# Airsensor.net
KiCad netlist of a schematic drawn in EAGLE
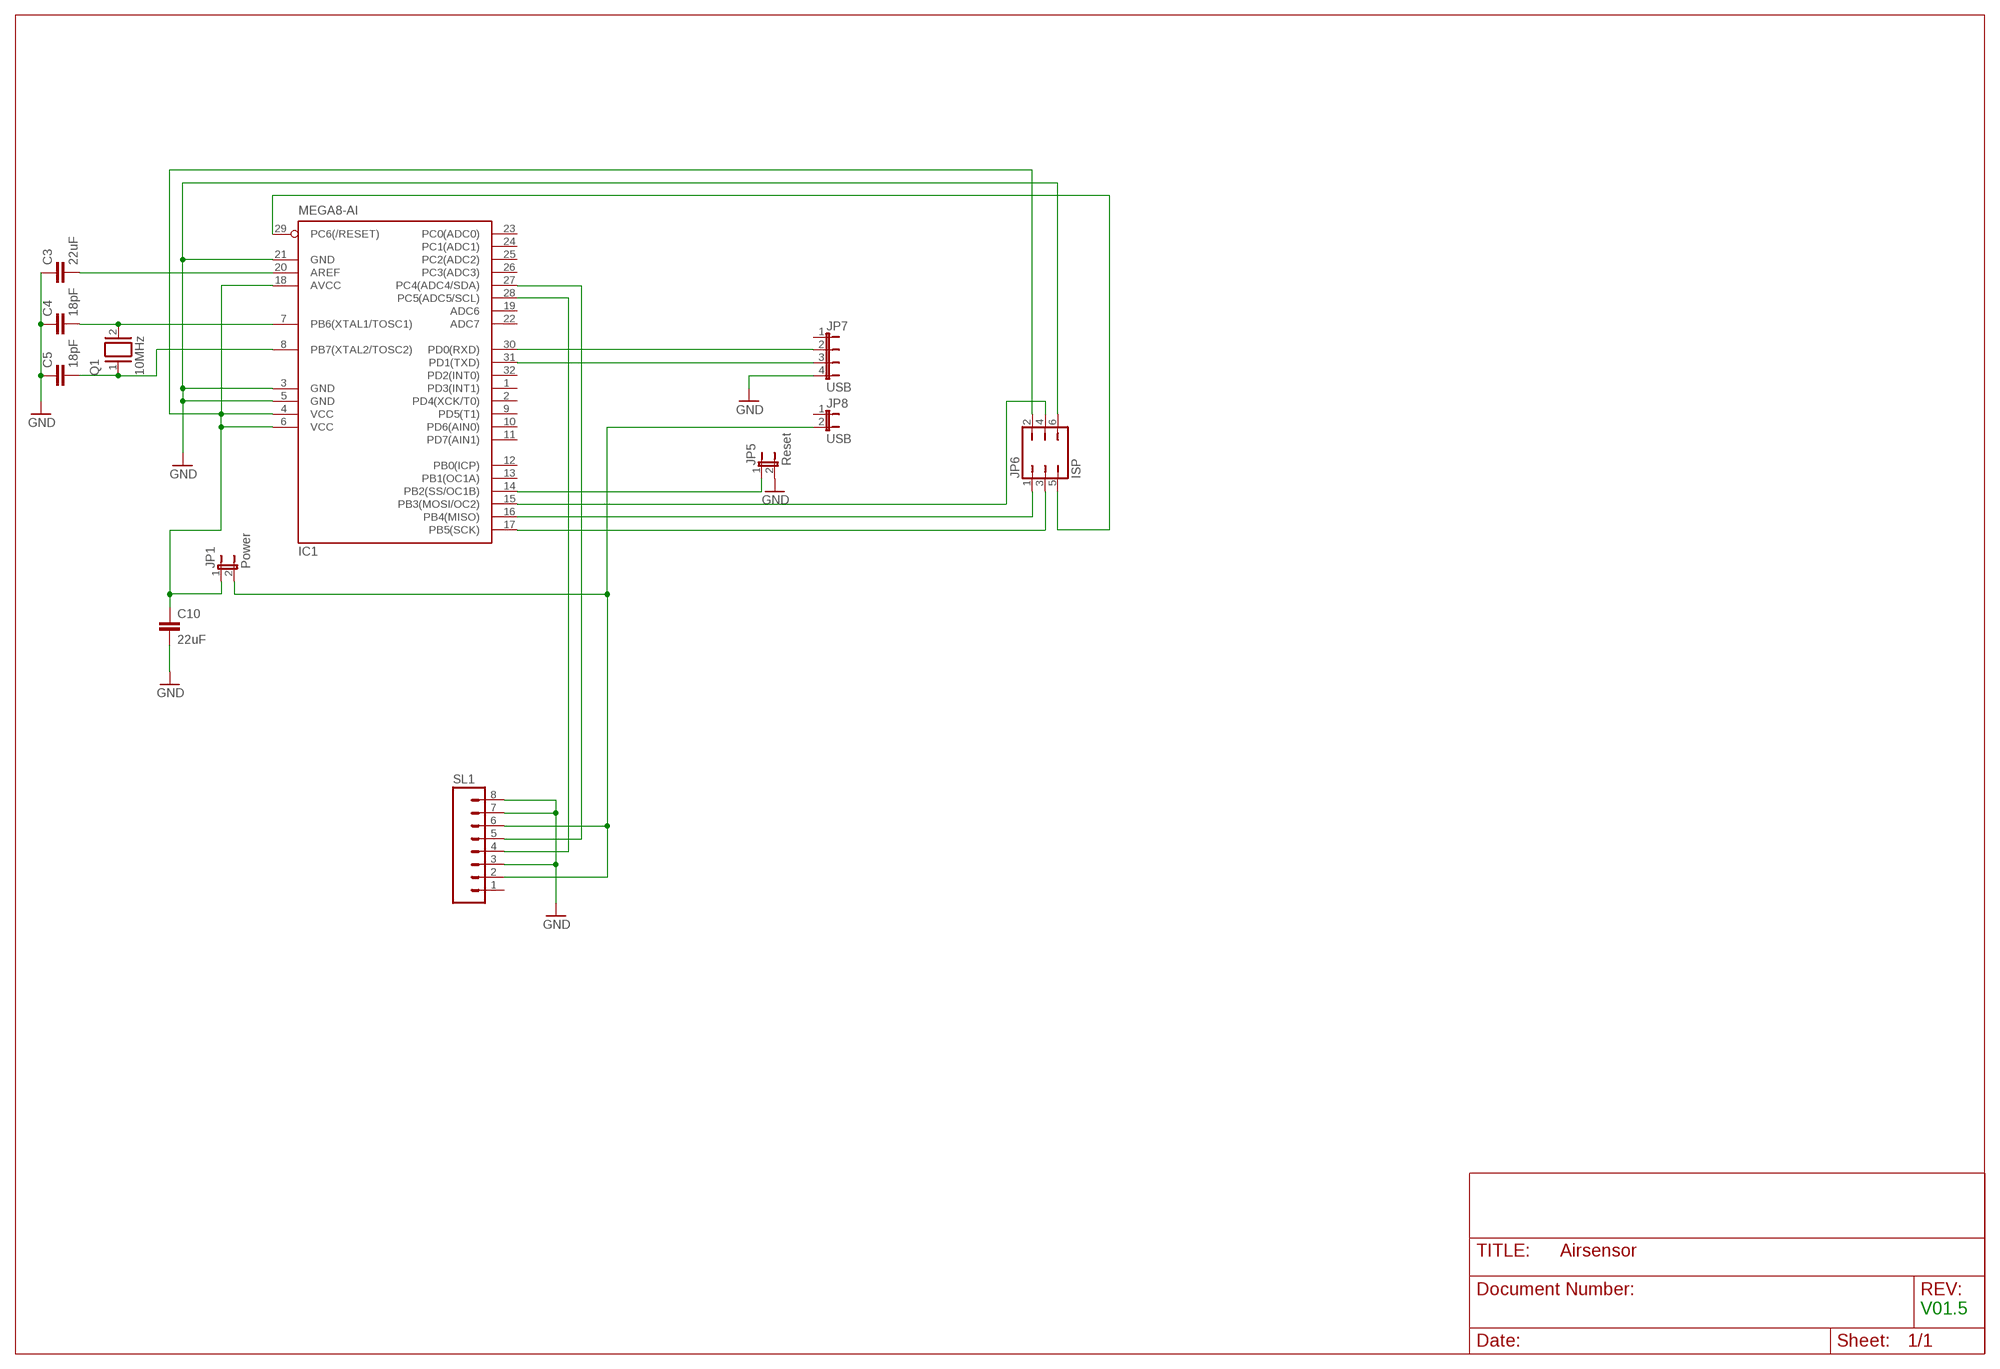
[diagram p0: schematic, sheet 1]

(export (version "E")
  (design (tool "Eeschema 10.0.6"))
  (components
    (comp (ref "C3")
      (value "22uF")
      (footprint "eagle-import:C1206")
      (libsource (lib "eagle-import") (part "C-EUC1206"))
    )
    (comp (ref "C4")
      (value "18pF")
      (footprint "eagle-import:C025-025X050")
      (libsource (lib "eagle-import") (part "resistor_C-EU025-025X050"))
    )
    (comp (ref "C5")
      (value "18pF")
      (footprint "eagle-import:C025-025X050")
      (libsource (lib "eagle-import") (part "resistor_C-EU025-025X050"))
    )
    (comp (ref "C10")
      (value "22uF")
      (footprint "eagle-import:C1206")
      (libsource (lib "eagle-import") (part "C-EUC1206"))
    )
    (comp (ref "IC1")
      (value "MEGA8-AI")
      (footprint "eagle-import:TQFP32-08")
      (fields (field (name "MPN") "ATMEGA8-16AU"))
      (libsource (lib "eagle-import") (part "MEGA8-AI"))
    )
    (comp (ref "JP1")
      (value "Power")
      (footprint "eagle-import:JP1")
      (libsource (lib "eagle-import") (part "JP1E"))
    )
    (comp (ref "JP5")
      (value "Reset")
      (footprint "eagle-import:JP1")
      (libsource (lib "eagle-import") (part "JP1E"))
    )
    (comp (ref "JP6")
      (value "ISP")
      (footprint "eagle-import:JP3Q")
      (libsource (lib "eagle-import") (part "JP3Q"))
    )
    (comp (ref "JP7")
      (value "USB")
      (footprint "eagle-import:JP4")
      (libsource (lib "eagle-import") (part "JP4E"))
    )
    (comp (ref "JP8")
      (value "USB")
      (footprint "eagle-import:JP1")
      (libsource (lib "eagle-import") (part "JP1E"))
    )
    (comp (ref "Q1")
      (value "10MHz")
      (footprint "eagle-import:QS")
      (libsource (lib "eagle-import") (part "XTAL/S"))
    )
    (comp (ref "SL1")
      (value "M08")
      (footprint "eagle-import:08P")
      (libsource (lib "eagle-import") (part "M08"))
    )
  )
  (nets
    (net (code "1") (name "GND") (class "Default")
      (node (ref "C10") (pin "2") (pinfunction "2_2") (pintype "passive"))
      (node (ref "C3") (pin "1") (pinfunction "1_1") (pintype "passive"))
      (node (ref "C4") (pin "1") (pinfunction "1_1") (pintype "passive"))
      (node (ref "C5") (pin "1") (pinfunction "1_1") (pintype "passive"))
      (node (ref "IC1") (pin "21") (pinfunction "GND_21") (pintype "power_in"))
      (node (ref "IC1") (pin "3") (pinfunction "GND_3") (pintype "power_in"))
      (node (ref "IC1") (pin "5") (pinfunction "GND_5") (pintype "power_in"))
      (node (ref "JP5") (pin "2") (pinfunction "2_2") (pintype "passive"))
      (node (ref "JP6") (pin "6") (pinfunction "6_6") (pintype "passive"))
      (node (ref "JP7") (pin "4") (pinfunction "4_4") (pintype "passive"))
      (node (ref "SL1") (pin "3") (pinfunction "3_3") (pintype "passive"))
      (node (ref "SL1") (pin "7") (pinfunction "7_7") (pintype "passive"))
      (node (ref "SL1") (pin "8") (pinfunction "8_8") (pintype "passive"))
    )
    (net (code "2") (name "Net-(IC1-AREF)") (class "Default")
      (node (ref "C3") (pin "2") (pinfunction "2_2") (pintype "passive"))
      (node (ref "IC1") (pin "20") (pinfunction "AREF_20") (pintype "passive"))
    )
    (net (code "3") (name "Net-(IC1-AVCC)") (class "Default")
      (node (ref "C10") (pin "1") (pinfunction "1_1") (pintype "passive"))
      (node (ref "IC1") (pin "18") (pinfunction "AVCC_18") (pintype "power_in"))
      (node (ref "IC1") (pin "4") (pinfunction "VCC_4") (pintype "power_in"))
      (node (ref "IC1") (pin "6") (pinfunction "VCC_6") (pintype "power_in"))
      (node (ref "JP1") (pin "1") (pinfunction "1_1") (pintype "passive"))
      (node (ref "JP6") (pin "2") (pinfunction "2_2") (pintype "passive"))
    )
    (net (code "4") (name "Net-(IC1-PB2(SS{slash}OC1B))") (class "Default")
      (node (ref "IC1") (pin "14") (pinfunction "PB2(SS/OC1B)_14") (pintype "bidirectional"))
      (node (ref "JP5") (pin "1") (pinfunction "1_1") (pintype "passive"))
    )
    (net (code "5") (name "Net-(IC1-PB3(MOSI{slash}OC2))") (class "Default")
      (node (ref "IC1") (pin "15") (pinfunction "PB3(MOSI/OC2)_15") (pintype "bidirectional"))
      (node (ref "JP6") (pin "4") (pinfunction "4_4") (pintype "passive"))
    )
    (net (code "6") (name "Net-(IC1-PB4(MISO))") (class "Default")
      (node (ref "IC1") (pin "16") (pinfunction "PB4(MISO)_16") (pintype "bidirectional"))
      (node (ref "JP6") (pin "1") (pinfunction "1_1") (pintype "passive"))
    )
    (net (code "7") (name "Net-(IC1-PB5(SCK))") (class "Default")
      (node (ref "IC1") (pin "17") (pinfunction "PB5(SCK)_17") (pintype "bidirectional"))
      (node (ref "JP6") (pin "3") (pinfunction "3_3") (pintype "passive"))
    )
    (net (code "8") (name "Net-(IC1-PB6(XTAL1{slash}TOSC1))") (class "Default")
      (node (ref "C4") (pin "2") (pinfunction "2_2") (pintype "passive"))
      (node (ref "IC1") (pin "7") (pinfunction "PB6(XTAL1/TOSC1)_7") (pintype "bidirectional"))
      (node (ref "Q1") (pin "2") (pinfunction "2_2") (pintype "passive"))
    )
    (net (code "9") (name "Net-(IC1-PB7(XTAL2{slash}TOSC2))") (class "Default")
      (node (ref "C5") (pin "2") (pinfunction "2_2") (pintype "passive"))
      (node (ref "IC1") (pin "8") (pinfunction "PB7(XTAL2/TOSC2)_8") (pintype "bidirectional"))
      (node (ref "Q1") (pin "1") (pinfunction "1_1") (pintype "passive"))
    )
    (net (code "10") (name "Net-(IC1-PC4(ADC4{slash}SDA))") (class "Default")
      (node (ref "IC1") (pin "27") (pinfunction "PC4(ADC4/SDA)_27") (pintype "bidirectional"))
      (node (ref "SL1") (pin "5") (pinfunction "5_5") (pintype "passive"))
    )
    (net (code "11") (name "Net-(IC1-PC5(ADC5{slash}SCL))") (class "Default")
      (node (ref "IC1") (pin "28") (pinfunction "PC5(ADC5/SCL)_28") (pintype "bidirectional"))
      (node (ref "SL1") (pin "4") (pinfunction "4_4") (pintype "passive"))
    )
    (net (code "12") (name "Net-(IC1-PC6({slash}RESET))") (class "Default")
      (node (ref "IC1") (pin "29") (pinfunction "PC6(/RESET)_29") (pintype "bidirectional"))
      (node (ref "JP6") (pin "5") (pinfunction "5_5") (pintype "passive"))
    )
    (net (code "13") (name "Net-(IC1-PD0(RXD))") (class "Default")
      (node (ref "IC1") (pin "30") (pinfunction "PD0(RXD)_30") (pintype "bidirectional"))
      (node (ref "JP7") (pin "2") (pinfunction "2_2") (pintype "passive"))
    )
    (net (code "14") (name "Net-(IC1-PD1(TXD))") (class "Default")
      (node (ref "IC1") (pin "31") (pinfunction "PD1(TXD)_31") (pintype "bidirectional"))
      (node (ref "JP7") (pin "3") (pinfunction "3_3") (pintype "passive"))
    )
    (net (code "15") (name "Net-(JP1-Pad2)") (class "Default")
      (node (ref "JP1") (pin "2") (pinfunction "2_2") (pintype "passive"))
      (node (ref "JP8") (pin "2") (pinfunction "2_2") (pintype "passive"))
      (node (ref "SL1") (pin "2") (pinfunction "2_2") (pintype "passive"))
      (node (ref "SL1") (pin "6") (pinfunction "6_6") (pintype "passive"))
    )
    (net (code "16") (name "unconnected-(IC1-ADC6-Pad19)") (class "Default")
      (node (ref "IC1") (pin "19") (pinfunction "ADC6_19") (pintype "bidirectional"))
    )
    (net (code "17") (name "unconnected-(IC1-ADC7-Pad22)") (class "Default")
      (node (ref "IC1") (pin "22") (pinfunction "ADC7_22") (pintype "bidirectional"))
    )
    (net (code "18") (name "unconnected-(IC1-PB0(ICP)-Pad12)") (class "Default")
      (node (ref "IC1") (pin "12") (pinfunction "PB0(ICP)_12") (pintype "bidirectional"))
    )
    (net (code "19") (name "unconnected-(IC1-PB1(OC1A)-Pad13)") (class "Default")
      (node (ref "IC1") (pin "13") (pinfunction "PB1(OC1A)_13") (pintype "bidirectional"))
    )
    (net (code "20") (name "unconnected-(IC1-PC0(ADC0)-Pad23)") (class "Default")
      (node (ref "IC1") (pin "23") (pinfunction "PC0(ADC0)_23") (pintype "bidirectional"))
    )
    (net (code "21") (name "unconnected-(IC1-PC1(ADC1)-Pad24)") (class "Default")
      (node (ref "IC1") (pin "24") (pinfunction "PC1(ADC1)_24") (pintype "bidirectional"))
    )
    (net (code "22") (name "unconnected-(IC1-PC2(ADC2)-Pad25)") (class "Default")
      (node (ref "IC1") (pin "25") (pinfunction "PC2(ADC2)_25") (pintype "bidirectional"))
    )
    (net (code "23") (name "unconnected-(IC1-PC3(ADC3)-Pad26)") (class "Default")
      (node (ref "IC1") (pin "26") (pinfunction "PC3(ADC3)_26") (pintype "bidirectional"))
    )
    (net (code "24") (name "unconnected-(IC1-PD2(INT0)-Pad32)") (class "Default")
      (node (ref "IC1") (pin "32") (pinfunction "PD2(INT0)_32") (pintype "bidirectional"))
    )
    (net (code "25") (name "unconnected-(IC1-PD3(INT1)-Pad1)") (class "Default")
      (node (ref "IC1") (pin "1") (pinfunction "PD3(INT1)_1") (pintype "bidirectional"))
    )
    (net (code "26") (name "unconnected-(IC1-PD4(XCK{slash}T0)-Pad2)") (class "Default")
      (node (ref "IC1") (pin "2") (pinfunction "PD4(XCK/T0)_2") (pintype "bidirectional"))
    )
    (net (code "27") (name "unconnected-(IC1-PD5(T1)-Pad9)") (class "Default")
      (node (ref "IC1") (pin "9") (pinfunction "PD5(T1)_9") (pintype "bidirectional"))
    )
    (net (code "28") (name "unconnected-(IC1-PD6(AIN0)-Pad10)") (class "Default")
      (node (ref "IC1") (pin "10") (pinfunction "PD6(AIN0)_10") (pintype "bidirectional"))
    )
    (net (code "29") (name "unconnected-(IC1-PD7(AIN1)-Pad11)") (class "Default")
      (node (ref "IC1") (pin "11") (pinfunction "PD7(AIN1)_11") (pintype "bidirectional"))
    )
    (net (code "30") (name "unconnected-(JP7-Pad1)") (class "Default")
      (node (ref "JP7") (pin "1") (pinfunction "1_1") (pintype "passive"))
    )
    (net (code "31") (name "unconnected-(JP8-Pad1)") (class "Default")
      (node (ref "JP8") (pin "1") (pinfunction "1_1") (pintype "passive"))
    )
    (net (code "32") (name "unconnected-(SL1-Pad1)") (class "Default")
      (node (ref "SL1") (pin "1") (pinfunction "1_1") (pintype "passive"))
    )
  )
)
